# LaunchSys_V1.net
KiCad netlist of a schematic drawn in EAGLE
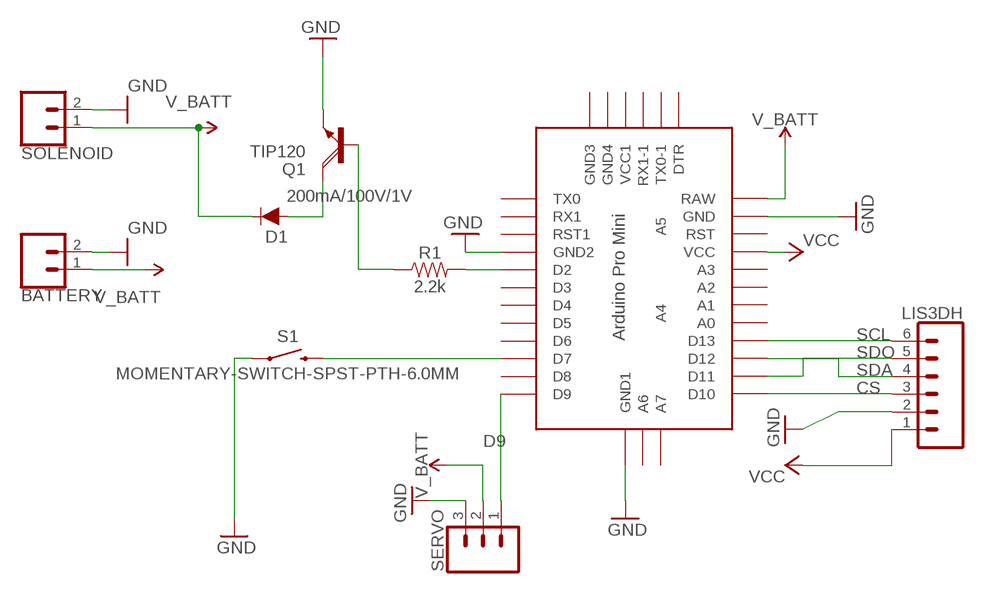
[diagram p0: schematic, sheet 1]

(export (version "E")
  (design (tool "Eeschema 10.0.6"))
  (components
    (comp (ref "BATTERY")
      (value "CONN_02")
      (footprint "eagle-import:1X02")
      (libsource (lib "eagle-import") (part "CONN_02"))
    )
    (comp (ref "D1")
      (value "200mA/100V/1V")
      (footprint "eagle-import:DIODE-1N4148")
      (libsource (lib "eagle-import") (part "DIODE-1N4148"))
    )
    (comp (ref "LIS3DH")
      (value "CONN_06SILK_FEMALE_PTH")
      (footprint "eagle-import:1X06")
      (libsource (lib "eagle-import") (part "CONN_06SILK_FEMALE_PTH"))
    )
    (comp (ref "Q1")
      (value "TIP120")
      (footprint "eagle-import:TO220AH")
      (libsource (lib "eagle-import") (part "TIP120"))
    )
    (comp (ref "R1")
      (value "2.2k")
      (footprint "eagle-import:AXIAL-0.3")
      (libsource (lib "eagle-import") (part "100KOHM-HORIZ-1/4W-5%"))
    )
    (comp (ref "S1")
      (value "MOMENTARY-SWITCH-SPST-PTH-6.0MM")
      (footprint "eagle-import:TACTILE_SWITCH_PTH_6.0MM")
      (libsource (lib "eagle-import") (part "MOMENTARY-SWITCH-SPST-PTH-6.0MM"))
    )
    (comp (ref "SERVO")
      (value "CONN_03")
      (footprint "eagle-import:1X03")
      (libsource (lib "eagle-import") (part "CONN_03"))
    )
    (comp (ref "SOLENOID")
      (value "CONN_02")
      (footprint "eagle-import:1X02")
      (libsource (lib "eagle-import") (part "CONN_02"))
    )
    (comp (ref "U$1")
      (value "ABK-PRO-MINI")
      (footprint "eagle-import:ABK-PRO-MINI")
      (libsource (lib "eagle-import") (part "ABK-PRO-MINI"))
    )
  )
  (nets
    (net (code "1") (name "/CS") (class "Default")
      (node (ref "LIS3DH") (pin "3") (pinfunction "3_3") (pintype "passive"))
      (node (ref "U$1") (pin "D10") (pinfunction "D10_D10") (pintype "bidirectional"))
    )
    (net (code "2") (name "/D9") (class "Default")
      (node (ref "SERVO") (pin "1") (pinfunction "1_1") (pintype "passive"))
      (node (ref "U$1") (pin "D9") (pinfunction "D9_D9") (pintype "bidirectional"))
    )
    (net (code "3") (name "/SCL") (class "Default")
      (node (ref "LIS3DH") (pin "6") (pinfunction "6_6") (pintype "passive"))
      (node (ref "U$1") (pin "D13") (pinfunction "D13_D13") (pintype "bidirectional"))
    )
    (net (code "4") (name "/SDA") (class "Default")
      (node (ref "LIS3DH") (pin "4") (pinfunction "4_4") (pintype "passive"))
      (node (ref "U$1") (pin "D12") (pinfunction "D12_D12") (pintype "bidirectional"))
    )
    (net (code "5") (name "/SDO") (class "Default")
      (node (ref "LIS3DH") (pin "5") (pinfunction "5_5") (pintype "passive"))
      (node (ref "U$1") (pin "D11") (pinfunction "D11_D11") (pintype "bidirectional"))
    )
    (net (code "6") (name "GND") (class "Default")
      (node (ref "BATTERY") (pin "2") (pinfunction "2_2") (pintype "passive"))
      (node (ref "LIS3DH") (pin "2") (pinfunction "2_2") (pintype "passive"))
      (node (ref "Q1") (pin "E") (pinfunction "E_E") (pintype "passive"))
      (node (ref "S1") (pin "1") (pinfunction "1_1") (pintype "passive"))
      (node (ref "SERVO") (pin "3") (pinfunction "3_3") (pintype "passive"))
      (node (ref "SOLENOID") (pin "2") (pinfunction "2_2") (pintype "passive"))
      (node (ref "U$1") (pin "GND") (pinfunction "GND_GND") (pintype "bidirectional"))
      (node (ref "U$1") (pin "GND1") (pinfunction "GND2_GND1") (pintype "bidirectional"))
      (node (ref "U$1") (pin "GND4") (pinfunction "GND1_GND4") (pintype "bidirectional"))
    )
    (net (code "7") (name "Net-(D1-PadA)") (class "Default")
      (node (ref "D1") (pin "A") (pinfunction "A_A") (pintype "passive"))
      (node (ref "Q1") (pin "C") (pinfunction "C_C") (pintype "passive"))
    )
    (net (code "8") (name "Net-(R1-1)") (class "Default")
      (node (ref "Q1") (pin "B") (pinfunction "B_B") (pintype "passive"))
      (node (ref "R1") (pin "P$1") (pinfunction "1_P$1") (pintype "passive"))
    )
    (net (code "9") (name "Net-(R1-2)") (class "Default")
      (node (ref "R1") (pin "P$2") (pinfunction "2_P$2") (pintype "passive"))
      (node (ref "U$1") (pin "D2") (pinfunction "D2_D2") (pintype "bidirectional"))
    )
    (net (code "10") (name "Net-(S1-2)") (class "Default")
      (node (ref "S1") (pin "3") (pinfunction "2_3") (pintype "passive"))
      (node (ref "U$1") (pin "D7") (pinfunction "D7_D7") (pintype "bidirectional"))
    )
    (net (code "11") (name "VCC") (class "Default")
      (node (ref "LIS3DH") (pin "1") (pinfunction "1_1") (pintype "passive"))
      (node (ref "U$1") (pin "VCC") (pinfunction "VCC_VCC") (pintype "bidirectional"))
    )
    (net (code "12") (name "V_BATT") (class "Default")
      (node (ref "BATTERY") (pin "1") (pinfunction "1_1") (pintype "passive"))
      (node (ref "D1") (pin "C") (pinfunction "C_C") (pintype "passive"))
      (node (ref "SERVO") (pin "2") (pinfunction "2_2") (pintype "passive"))
      (node (ref "SOLENOID") (pin "1") (pinfunction "1_1") (pintype "passive"))
      (node (ref "U$1") (pin "RAW") (pinfunction "RAW_RAW") (pintype "bidirectional"))
    )
    (net (code "13") (name "unconnected-(U$1-GND3-PadGND2)") (class "Default")
      (node (ref "U$1") (pin "GND2") (pinfunction "GND3_GND2") (pintype "bidirectional"))
    )
    (net (code "14") (name "unconnected-(U$1-GND4-PadGND3)") (class "Default")
      (node (ref "U$1") (pin "GND3") (pinfunction "GND4_GND3") (pintype "bidirectional"))
    )
    (net (code "15") (name "unconnected-(U$1-PadA0)") (class "Default")
      (node (ref "U$1") (pin "A0") (pinfunction "A0_A0") (pintype "bidirectional"))
    )
    (net (code "16") (name "unconnected-(U$1-PadA1)") (class "Default")
      (node (ref "U$1") (pin "A1") (pinfunction "A1_A1") (pintype "bidirectional"))
    )
    (net (code "17") (name "unconnected-(U$1-PadA2)") (class "Default")
      (node (ref "U$1") (pin "A2") (pinfunction "A2_A2") (pintype "bidirectional"))
    )
    (net (code "18") (name "unconnected-(U$1-PadA3)") (class "Default")
      (node (ref "U$1") (pin "A3") (pinfunction "A3_A3") (pintype "bidirectional"))
    )
    (net (code "19") (name "unconnected-(U$1-PadA4)") (class "Default")
      (node (ref "U$1") (pin "A4") (pinfunction "A4_A4") (pintype "bidirectional"))
    )
    (net (code "20") (name "unconnected-(U$1-PadA5)") (class "Default")
      (node (ref "U$1") (pin "A5") (pinfunction "A5_A5") (pintype "bidirectional"))
    )
    (net (code "21") (name "unconnected-(U$1-PadA6)") (class "Default")
      (node (ref "U$1") (pin "A6") (pinfunction "A6_A6") (pintype "bidirectional"))
    )
    (net (code "22") (name "unconnected-(U$1-PadA7)") (class "Default")
      (node (ref "U$1") (pin "A7") (pinfunction "A7_A7") (pintype "bidirectional"))
    )
    (net (code "23") (name "unconnected-(U$1-PadD3)") (class "Default")
      (node (ref "U$1") (pin "D3") (pinfunction "D3_D3") (pintype "bidirectional"))
    )
    (net (code "24") (name "unconnected-(U$1-PadD4)") (class "Default")
      (node (ref "U$1") (pin "D4") (pinfunction "D4_D4") (pintype "bidirectional"))
    )
    (net (code "25") (name "unconnected-(U$1-PadD5)") (class "Default")
      (node (ref "U$1") (pin "D5") (pinfunction "D5_D5") (pintype "bidirectional"))
    )
    (net (code "26") (name "unconnected-(U$1-PadD6)") (class "Default")
      (node (ref "U$1") (pin "D6") (pinfunction "D6_D6") (pintype "bidirectional"))
    )
    (net (code "27") (name "unconnected-(U$1-PadD8)") (class "Default")
      (node (ref "U$1") (pin "D8") (pinfunction "D8_D8") (pintype "bidirectional"))
    )
    (net (code "28") (name "unconnected-(U$1-PadDTR)") (class "Default")
      (node (ref "U$1") (pin "DTR") (pinfunction "DTR_DTR") (pintype "bidirectional"))
    )
    (net (code "29") (name "unconnected-(U$1-PadRST)") (class "Default")
      (node (ref "U$1") (pin "RST") (pinfunction "RST_RST") (pintype "bidirectional"))
    )
    (net (code "30") (name "unconnected-(U$1-PadRST1)") (class "Default")
      (node (ref "U$1") (pin "RST1") (pinfunction "RST1_RST1") (pintype "bidirectional"))
    )
    (net (code "31") (name "unconnected-(U$1-PadRX1)") (class "Default")
      (node (ref "U$1") (pin "RX1") (pinfunction "RX1_RX1") (pintype "bidirectional"))
    )
    (net (code "32") (name "unconnected-(U$1-PadRX1-1)") (class "Default")
      (node (ref "U$1") (pin "RX1-1") (pinfunction "RX1-1_RX1-1") (pintype "bidirectional"))
    )
    (net (code "33") (name "unconnected-(U$1-PadTX0)") (class "Default")
      (node (ref "U$1") (pin "TX0") (pinfunction "TX0_TX0") (pintype "bidirectional"))
    )
    (net (code "34") (name "unconnected-(U$1-PadTX0-1)") (class "Default")
      (node (ref "U$1") (pin "TX0-1") (pinfunction "TX0-1_TX0-1") (pintype "bidirectional"))
    )
    (net (code "35") (name "unconnected-(U$1-PadVCC1)") (class "Default")
      (node (ref "U$1") (pin "VCC1") (pinfunction "VCC1_VCC1") (pintype "bidirectional"))
    )
  )
)
